# regulation-level-shifter-mk-1_0.net
KiCad netlist of a schematic drawn in EAGLE
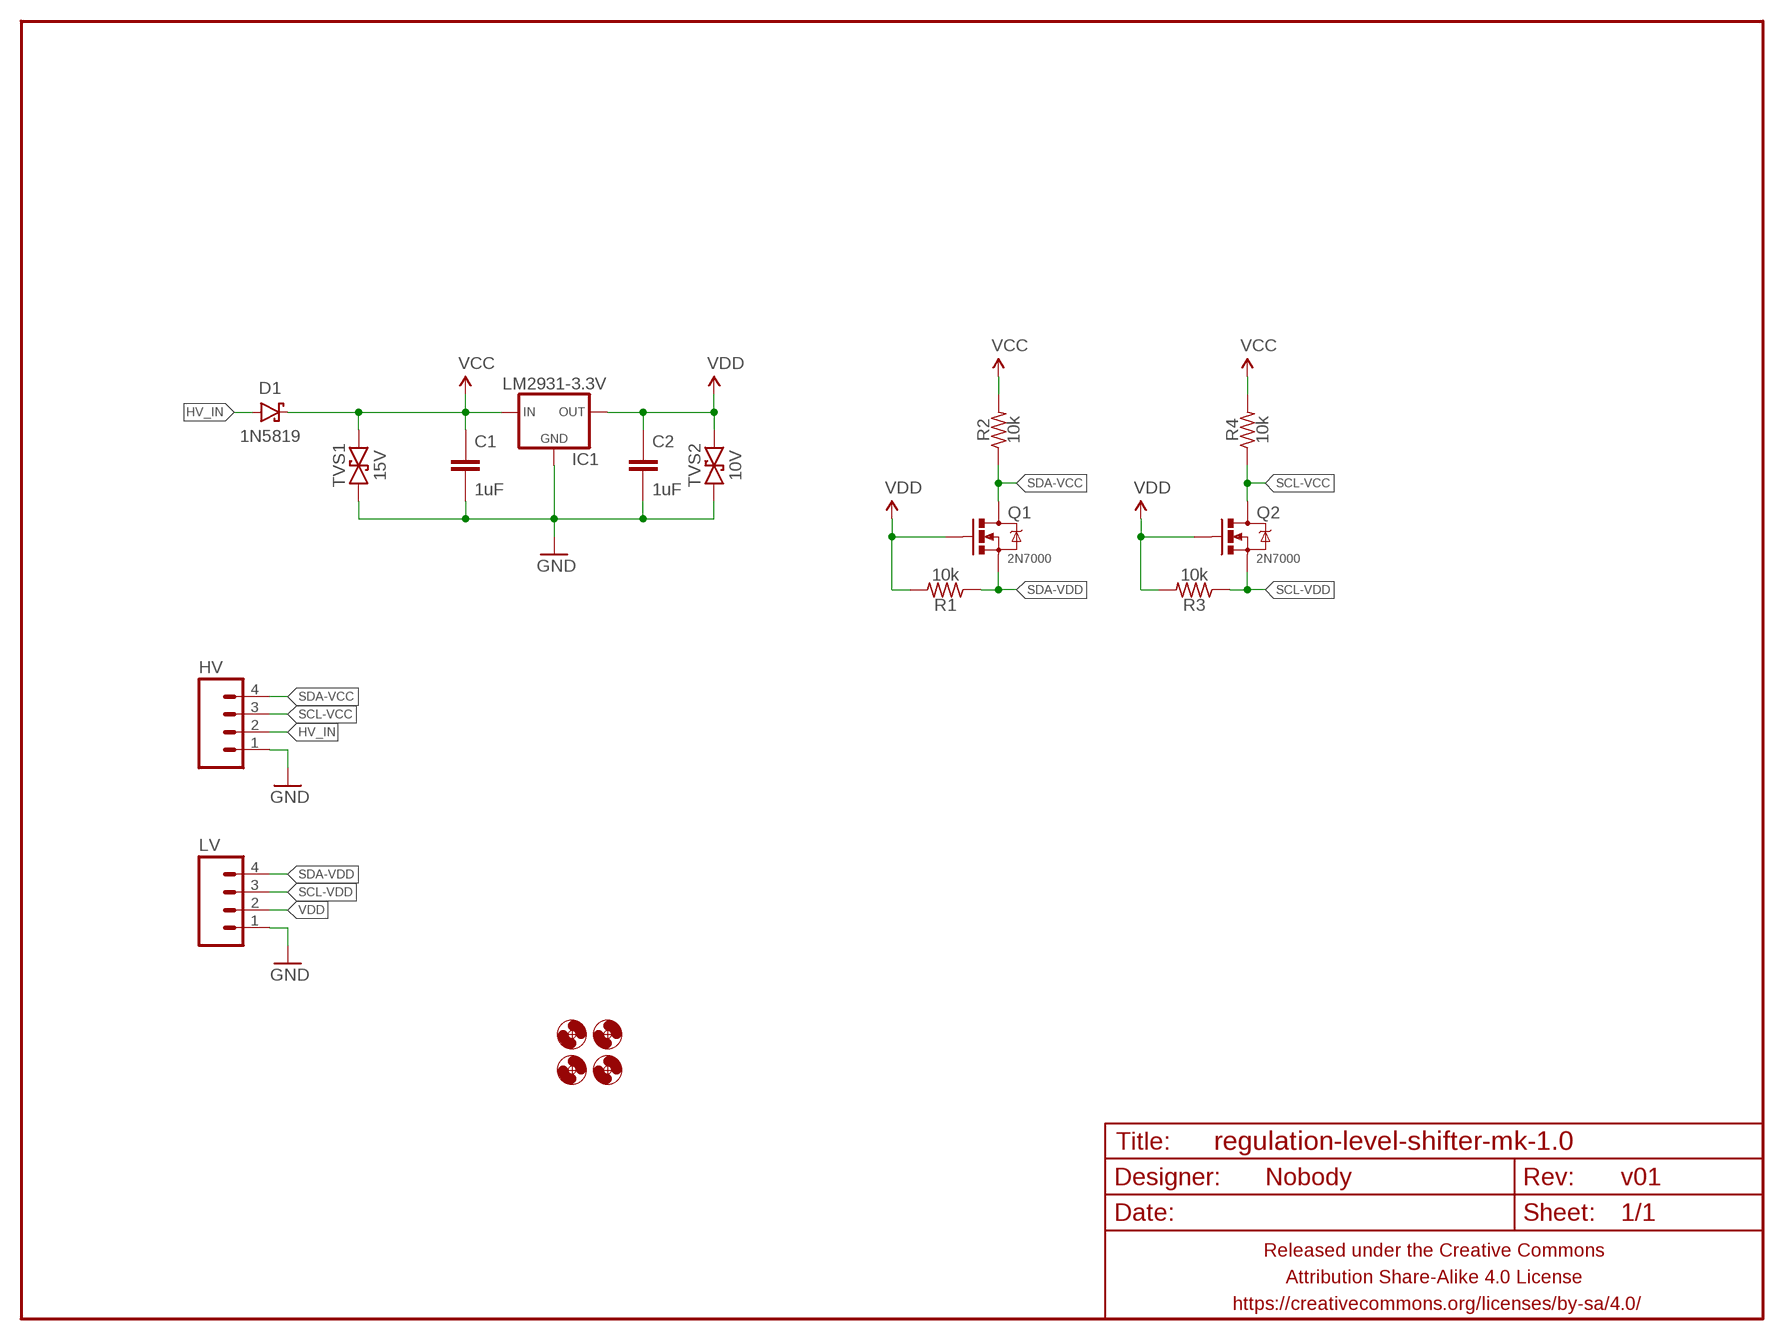
[diagram p0: schematic, sheet 1]

(export (version "E")
  (design (tool "Eeschema 10.0.6"))
  (components
    (comp (ref "C1")
      (value "1uF")
      (footprint "eagle-import:C025-024X044")
      (libsource (lib "eagle-import") (part "CAPACITOR-CERAMIC025-024X044"))
    )
    (comp (ref "C2")
      (value "1uF")
      (footprint "eagle-import:C025-024X044")
      (libsource (lib "eagle-import") (part "CAPACITOR-CERAMIC025-024X044"))
    )
    (comp (ref "D1")
      (value "1N5819")
      (footprint "eagle-import:DIODE-10.16MM")
      (libsource (lib "eagle-import") (part "DIODE-SCHOTTKYPTH-10.16MM"))
    )
    (comp (ref "FRAME1")
      (value "FRAME-LETTERNO_PACKAGE")
      (footprint "eagle-import:DUMMY")
      (fields (field (name "DESIGNER") "Nobody"))
      (libsource (lib "eagle-import") (part "FRAME-LETTERNO_PACKAGE"))
    )
    (comp (ref "H1")
      (value "HOLE#2")
      (footprint "eagle-import:HOLE-#2")
      (libsource (lib "eagle-import") (part "HOLE#2"))
    )
    (comp (ref "H2")
      (value "HOLE#2")
      (footprint "eagle-import:HOLE-#2")
      (libsource (lib "eagle-import") (part "HOLE#2"))
    )
    (comp (ref "H3")
      (value "HOLE#2")
      (footprint "eagle-import:HOLE-#2")
      (libsource (lib "eagle-import") (part "HOLE#2"))
    )
    (comp (ref "H4")
      (value "HOLE#2")
      (footprint "eagle-import:HOLE-#2")
      (libsource (lib "eagle-import") (part "HOLE#2"))
    )
    (comp (ref "HV")
      (value "M04PTH")
      (footprint "eagle-import:1X04-PTH-VERT")
      (libsource (lib "eagle-import") (part "M04PTH"))
    )
    (comp (ref "IC1")
      (value "LM2931-3.3V")
      (footprint "eagle-import:TO-92-AMMO")
      (libsource (lib "eagle-import") (part "V_REG_78XXTO-92-INLINE"))
    )
    (comp (ref "LV")
      (value "M04PTH")
      (footprint "eagle-import:1X04-PTH-VERT")
      (libsource (lib "eagle-import") (part "M04PTH"))
    )
    (comp (ref "Q1")
      (value "2N7000")
      (footprint "eagle-import:TO-92-AMMO")
      (libsource (lib "eagle-import") (part "MOSFET-NCHANNEL2N7000-AMMO"))
    )
    (comp (ref "Q2")
      (value "2N7000")
      (footprint "eagle-import:TO-92-AMMO")
      (libsource (lib "eagle-import") (part "MOSFET-NCHANNEL2N7000-AMMO"))
    )
    (comp (ref "R1")
      (value "10k")
      (footprint "eagle-import:RESISTOR-AXIAL-PTH-5.08MM")
      (libsource (lib "eagle-import") (part "RESISTORPTH-AXIAL-5.08MM"))
    )
    (comp (ref "R2")
      (value "10k")
      (footprint "eagle-import:RESISTOR-AXIAL-PTH-5.08MM")
      (libsource (lib "eagle-import") (part "RESISTORPTH-AXIAL-5.08MM"))
    )
    (comp (ref "R3")
      (value "10k")
      (footprint "eagle-import:RESISTOR-AXIAL-PTH-5.08MM")
      (libsource (lib "eagle-import") (part "RESISTORPTH-AXIAL-5.08MM"))
    )
    (comp (ref "R4")
      (value "10k")
      (footprint "eagle-import:RESISTOR-AXIAL-PTH-5.08MM")
      (libsource (lib "eagle-import") (part "RESISTORPTH-AXIAL-5.08MM"))
    )
    (comp (ref "TVS1")
      (value "15V")
      (footprint "eagle-import:DO-41-TVS-BI-10.16MM")
      (libsource (lib "eagle-import") (part "TVSDO-41-10.16MM"))
    )
    (comp (ref "TVS2")
      (value "10V")
      (footprint "eagle-import:DO-41-TVS-BI-10.16MM")
      (libsource (lib "eagle-import") (part "TVSDO-41-10.16MM"))
    )
  )
  (nets
    (net (code "1") (name "GND") (class "Default")
      (node (ref "C1") (pin "2") (pinfunction "2_2") (pintype "passive"))
      (node (ref "C2") (pin "2") (pinfunction "2_2") (pintype "passive"))
      (node (ref "HV") (pin "1") (pinfunction "1_1") (pintype "passive"))
      (node (ref "IC1") (pin "2") (pinfunction "GND_2") (pintype "bidirectional"))
      (node (ref "LV") (pin "1") (pinfunction "1_1") (pintype "passive"))
      (node (ref "TVS1") (pin "P$1") (pinfunction "1_P$1") (pintype "passive"))
      (node (ref "TVS2") (pin "P$1") (pinfunction "1_P$1") (pintype "passive"))
    )
    (net (code "2") (name "HV_IN") (class "Default")
      (node (ref "D1") (pin "A") (pinfunction "A_A") (pintype "passive"))
      (node (ref "HV") (pin "2") (pinfunction "2_2") (pintype "passive"))
    )
    (net (code "3") (name "SCL-VCC") (class "Default")
      (node (ref "HV") (pin "3") (pinfunction "3_3") (pintype "passive"))
      (node (ref "Q2") (pin "3") (pinfunction "D_3") (pintype "passive"))
      (node (ref "R4") (pin "P$1") (pinfunction "1_P$1") (pintype "passive"))
    )
    (net (code "4") (name "SCL-VDD") (class "Default")
      (node (ref "LV") (pin "3") (pinfunction "3_3") (pintype "passive"))
      (node (ref "Q2") (pin "1") (pinfunction "S_1") (pintype "passive"))
      (node (ref "R3") (pin "P$1") (pinfunction "1_P$1") (pintype "passive"))
    )
    (net (code "5") (name "SDA-VCC") (class "Default")
      (node (ref "HV") (pin "4") (pinfunction "4_4") (pintype "passive"))
      (node (ref "Q1") (pin "3") (pinfunction "D_3") (pintype "passive"))
      (node (ref "R2") (pin "P$1") (pinfunction "1_P$1") (pintype "passive"))
    )
    (net (code "6") (name "SDA-VDD") (class "Default")
      (node (ref "LV") (pin "4") (pinfunction "4_4") (pintype "passive"))
      (node (ref "Q1") (pin "1") (pinfunction "S_1") (pintype "passive"))
      (node (ref "R1") (pin "P$1") (pinfunction "1_P$1") (pintype "passive"))
    )
    (net (code "7") (name "VCC") (class "Default")
      (node (ref "C1") (pin "1") (pinfunction "1_1") (pintype "passive"))
      (node (ref "D1") (pin "C") (pinfunction "C_C") (pintype "passive"))
      (node (ref "IC1") (pin "1") (pinfunction "IN_1") (pintype "bidirectional"))
      (node (ref "R2") (pin "P$2") (pinfunction "2_P$2") (pintype "passive"))
      (node (ref "R4") (pin "P$2") (pinfunction "2_P$2") (pintype "passive"))
      (node (ref "TVS1") (pin "P$2") (pinfunction "2_P$2") (pintype "passive"))
    )
    (net (code "8") (name "VDD") (class "Default")
      (node (ref "C2") (pin "1") (pinfunction "1_1") (pintype "passive"))
      (node (ref "IC1") (pin "3") (pinfunction "OUT_3") (pintype "bidirectional"))
      (node (ref "LV") (pin "2") (pinfunction "2_2") (pintype "passive"))
      (node (ref "Q1") (pin "2") (pinfunction "G_2") (pintype "passive"))
      (node (ref "Q2") (pin "2") (pinfunction "G_2") (pintype "passive"))
      (node (ref "R1") (pin "P$2") (pinfunction "2_P$2") (pintype "passive"))
      (node (ref "R3") (pin "P$2") (pinfunction "2_P$2") (pintype "passive"))
      (node (ref "TVS2") (pin "P$2") (pinfunction "2_P$2") (pintype "passive"))
    )
  )
)
